# Regulators.net
KiCad netlist of a schematic drawn in Altium Designer
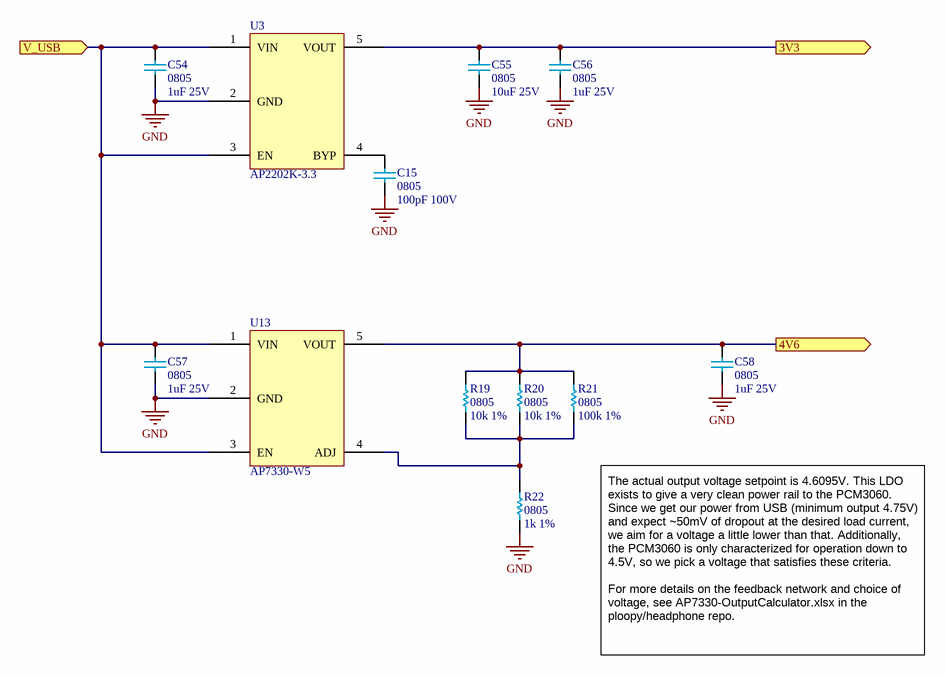
[diagram p0: Regulators.SchDoc]

(export (version "E")
  (design (tool "Eeschema 10.0.6"))
  (components
    (comp (ref "C15")
      (value "0805")
      (footprint "0805")
      (description "0805, X5R or better")
      (fields (field (name "ALTIUM_VALUE") "100pF 100V"))
      (libsource (lib "Chip_Passives") (part "Cap 100pF 100V"))
    )
    (comp (ref "C54")
      (value "0805")
      (footprint "0805")
      (description "0805, X5R or better")
      (fields (field (name "ALTIUM_VALUE") "1uF 25V"))
      (libsource (lib "Chip_Passives") (part "Cap 1uF 25V"))
    )
    (comp (ref "C55")
      (value "0805")
      (footprint "0805")
      (description "0805, X5R or better")
      (fields (field (name "ALTIUM_VALUE") "10uF 25V"))
      (libsource (lib "Chip_Passives") (part "Cap 10uF 25V"))
    )
    (comp (ref "C56")
      (value "0805")
      (footprint "0805")
      (description "0805, X5R or better")
      (fields (field (name "ALTIUM_VALUE") "1uF 25V"))
      (libsource (lib "Chip_Passives") (part "Cap 1uF 25V"))
    )
    (comp (ref "C57")
      (value "0805")
      (footprint "0805")
      (description "0805, X5R or better")
      (fields (field (name "ALTIUM_VALUE") "1uF 25V"))
      (libsource (lib "Chip_Passives") (part "Cap 1uF 25V"))
    )
    (comp (ref "C58")
      (value "0805")
      (footprint "0805")
      (description "0805, X5R or better")
      (fields (field (name "ALTIUM_VALUE") "1uF 25V"))
      (libsource (lib "Chip_Passives") (part "Cap 1uF 25V"))
    )
    (comp (ref "R19")
      (value "0805")
      (footprint "0805")
      (description "Chip resistor")
      (fields (field (name "ALTIUM_VALUE") "10k 1%"))
      (libsource (lib "Chip_Passives") (part "Res 10k 1% 0805"))
    )
    (comp (ref "R20")
      (value "0805")
      (footprint "0805")
      (description "Chip resistor")
      (fields (field (name "ALTIUM_VALUE") "10k 1%"))
      (libsource (lib "Chip_Passives") (part "Res 10k 1% 0805"))
    )
    (comp (ref "R21")
      (value "0805")
      (footprint "0805")
      (description "Chip resistor")
      (fields (field (name "ALTIUM_VALUE") "100k 1%"))
      (libsource (lib "Chip_Passives") (part "Res 100k 1% 0805"))
    )
    (comp (ref "R22")
      (value "0805")
      (footprint "0805")
      (description "Chip resistor, 1/8W 100PPM")
      (fields (field (name "ALTIUM_VALUE") "1k 1%"))
      (libsource (lib "Chip_Passives") (part "Res 1k 1% 0805"))
    )
    (comp (ref "U3")
      (value "AP2202K-3.3")
      (footprint "AP2202 - SOT95P270X145-5N")
      (description "3.3V 150mA LDO regulator")
      (libsource (lib "PowerSupply") (part "AP2202K-3.3"))
    )
    (comp (ref "U13")
      (value "AP7330-W5")
      (footprint "AP7330-W5 - SOT95P270X145-5N")
      (description "300mA HIGH PSRR LOW NOISE LDO WITH ENABLE")
      (libsource (lib "PowerSupply") (part "AP7330-W5"))
    )
  )
  (nets
    (net (code "1") (name "/3V3") (class "Default")
      (node (ref "C55") (pin "2") (pinfunction "2_2") (pintype "passive"))
      (node (ref "C56") (pin "2") (pinfunction "2_2") (pintype "passive"))
      (node (ref "U3") (pin "5") (pinfunction "VOUT_5") (pintype "passive"))
    )
    (net (code "2") (name "/4V6") (class "Default")
      (node (ref "C58") (pin "2") (pinfunction "2_2") (pintype "passive"))
      (node (ref "R19") (pin "2") (pinfunction "2_2") (pintype "passive"))
      (node (ref "R20") (pin "2") (pinfunction "2_2") (pintype "passive"))
      (node (ref "R21") (pin "2") (pinfunction "2_2") (pintype "passive"))
      (node (ref "U13") (pin "5") (pinfunction "VOUT_5") (pintype "passive"))
    )
    (net (code "3") (name "/V_USB") (class "Default")
      (node (ref "C54") (pin "2") (pinfunction "2_2") (pintype "passive"))
      (node (ref "C57") (pin "2") (pinfunction "2_2") (pintype "passive"))
      (node (ref "U13") (pin "1") (pinfunction "VIN_1") (pintype "passive"))
      (node (ref "U13") (pin "3") (pinfunction "EN_3") (pintype "passive"))
      (node (ref "U3") (pin "1") (pinfunction "VIN_1") (pintype "passive"))
      (node (ref "U3") (pin "3") (pinfunction "EN_3") (pintype "passive"))
    )
    (net (code "4") (name "GND") (class "Default")
      (node (ref "C15") (pin "1") (pinfunction "1_1") (pintype "passive"))
      (node (ref "C54") (pin "1") (pinfunction "1_1") (pintype "passive"))
      (node (ref "C55") (pin "1") (pinfunction "1_1") (pintype "passive"))
      (node (ref "C56") (pin "1") (pinfunction "1_1") (pintype "passive"))
      (node (ref "C57") (pin "1") (pinfunction "1_1") (pintype "passive"))
      (node (ref "C58") (pin "1") (pinfunction "1_1") (pintype "passive"))
      (node (ref "R22") (pin "1") (pinfunction "1_1") (pintype "passive"))
      (node (ref "U13") (pin "2") (pinfunction "GND_2") (pintype "passive"))
      (node (ref "U3") (pin "2") (pinfunction "GND_2") (pintype "passive"))
    )
    (net (code "5") (name "Net-(U3-BYP)") (class "Default")
      (node (ref "C15") (pin "2") (pinfunction "2_2") (pintype "passive"))
      (node (ref "U3") (pin "4") (pinfunction "BYP_4") (pintype "passive"))
    )
    (net (code "6") (name "Net-(U13-ADJ)") (class "Default")
      (node (ref "R19") (pin "1") (pinfunction "1_1") (pintype "passive"))
      (node (ref "R20") (pin "1") (pinfunction "1_1") (pintype "passive"))
      (node (ref "R21") (pin "1") (pinfunction "1_1") (pintype "passive"))
      (node (ref "R22") (pin "2") (pinfunction "2_2") (pintype "passive"))
      (node (ref "U13") (pin "4") (pinfunction "ADJ_4") (pintype "passive"))
    )
  )
)
